# myRelay.net
KiCad netlist of a schematic drawn in EAGLE
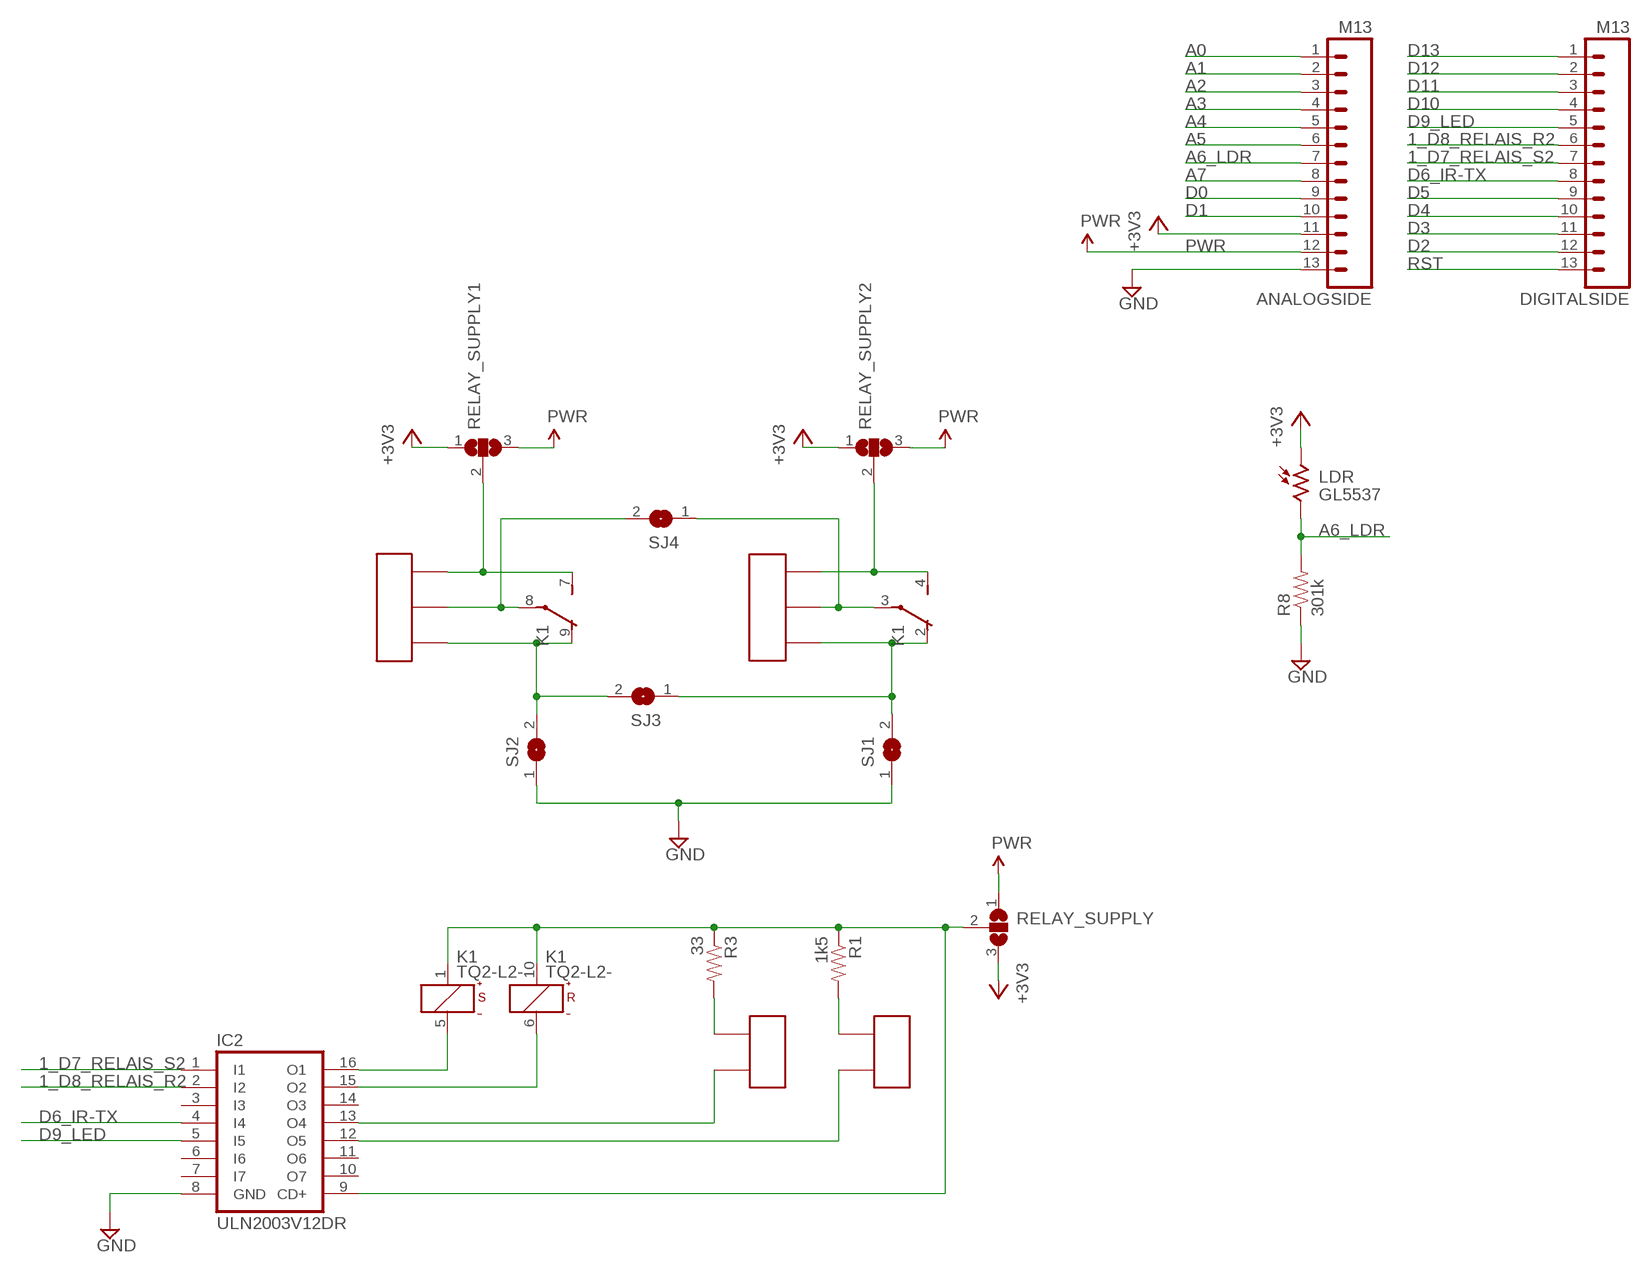
[diagram p0: schematic, sheet 1]

(export (version "E")
  (design (tool "Eeschema 10.0.6"))
  (components
    (comp (ref "ANALOGSIDE")
      (value "M13")
      (footprint "eagle-import:1X13")
      (libsource (lib "eagle-import") (part "M13"))
    )
    (comp (ref "DIGITALSIDE")
      (value "M13")
      (footprint "eagle-import:1X13")
      (libsource (lib "eagle-import") (part "M13"))
    )
    (comp (ref "IC2")
      (value "ULN2003V12DR")
      (footprint "eagle-import:SO16")
      (libsource (lib "eagle-import") (part "ULN2003AD"))
    )
    (comp (ref "K1")
      (value "TQ2-L2-")
      (footprint "eagle-import:TQ2")
      (fields
        (field (name "MF") "AROMAT/ MATSUSHITA")
        (field (name "MPN") "TQ2-L2-9V")
        (field (name "BUERKLIN") "30 G 7570")
        (field (name "MPN_1") "TQ2-L2-3V")
      )
      (libsource (lib "eagle-import") (part "TQ2?-L2-"))
    )
    (comp (ref "LDR")
      (value "GL5537")
      (footprint "eagle-import:M9960")
      (libsource (lib "eagle-import") (part "M9960_11A"))
    )
    (comp (ref "R1")
      (value "1k5")
      (footprint "eagle-import:0603-RES")
      (libsource (lib "eagle-import") (part "RESISTOR0603-RES"))
    )
    (comp (ref "R3")
      (value "33")
      (footprint "eagle-import:0603-RES")
      (libsource (lib "eagle-import") (part "RESISTOR0603-RES"))
    )
    (comp (ref "R8")
      (value "301k")
      (footprint "eagle-import:0603-RES")
      (libsource (lib "eagle-import") (part "RESISTOR0603-RES"))
    )
    (comp (ref "RELAY_SUPPLY")
      (value "SJ2WW")
      (footprint "eagle-import:SJ_2W")
      (libsource (lib "eagle-import") (part "SJ2WW"))
    )
    (comp (ref "RELAY_SUPPLY1")
      (value "SJ2WW")
      (footprint "eagle-import:SJ_2W")
      (libsource (lib "eagle-import") (part "SJ2WW"))
    )
    (comp (ref "RELAY_SUPPLY2")
      (value "SJ2WW")
      (footprint "eagle-import:SJ_2W")
      (libsource (lib "eagle-import") (part "SJ2WW"))
    )
    (comp (ref "SJ1")
      (value "SJW")
      (footprint "eagle-import:SJW")
      (libsource (lib "eagle-import") (part "SJW"))
    )
    (comp (ref "SJ2")
      (value "SJW")
      (footprint "eagle-import:SJW")
      (libsource (lib "eagle-import") (part "SJW"))
    )
    (comp (ref "SJ3")
      (value "SJW")
      (footprint "eagle-import:SJW")
      (libsource (lib "eagle-import") (part "SJW"))
    )
    (comp (ref "SJ4")
      (value "SJW")
      (footprint "eagle-import:SJW")
      (libsource (lib "eagle-import") (part "SJW"))
    )
    (comp (ref "U$1")
      (value "HDR_3PINLUMBERG_KRMC")
      (footprint "eagle-import:1X03_LUMBERG-KRMC_3,5MM")
      (libsource (lib "eagle-import") (part "HDR_3PINLUMBERG_KRMC"))
    )
    (comp (ref "U$2")
      (value "HDR_3PINLUMBERG_KRMC")
      (footprint "eagle-import:1X03_LUMBERG-KRMC_3,5MM")
      (libsource (lib "eagle-import") (part "HDR_3PINLUMBERG_KRMC"))
    )
    (comp (ref "U$3")
      (value "HDR_2PIN")
      (footprint "eagle-import:1X02_NS")
      (libsource (lib "eagle-import") (part "HDR_2PIN"))
    )
    (comp (ref "U$4")
      (value "HDR_2PIN")
      (footprint "eagle-import:1X02_NS")
      (libsource (lib "eagle-import") (part "HDR_2PIN"))
    )
  )
  (nets
    (net (code "1") (name "+3V3") (class "Default")
      (node (ref "ANALOGSIDE") (pin "11") (pinfunction "11_11") (pintype "passive"))
      (node (ref "LDR") (pin "1") (pinfunction "1_1") (pintype "passive"))
      (node (ref "RELAY_SUPPLY") (pin "3") (pinfunction "3_3") (pintype "passive"))
      (node (ref "RELAY_SUPPLY1") (pin "1") (pinfunction "1_1") (pintype "passive"))
      (node (ref "RELAY_SUPPLY2") (pin "1") (pinfunction "1_1") (pintype "passive"))
    )
    (net (code "2") (name "/1_D7_RELAIS_S2") (class "Default")
      (node (ref "DIGITALSIDE") (pin "7") (pinfunction "7_7") (pintype "passive"))
      (node (ref "IC2") (pin "1") (pinfunction "I1_1") (pintype "input"))
    )
    (net (code "3") (name "/1_D8_RELAIS_R2") (class "Default")
      (node (ref "DIGITALSIDE") (pin "6") (pinfunction "6_6") (pintype "passive"))
      (node (ref "IC2") (pin "2") (pinfunction "I2_2") (pintype "input"))
    )
    (net (code "4") (name "/A0") (class "Default")
      (node (ref "ANALOGSIDE") (pin "1") (pinfunction "1_1") (pintype "passive"))
    )
    (net (code "5") (name "/A1") (class "Default")
      (node (ref "ANALOGSIDE") (pin "2") (pinfunction "2_2") (pintype "passive"))
    )
    (net (code "6") (name "/A2") (class "Default")
      (node (ref "ANALOGSIDE") (pin "3") (pinfunction "3_3") (pintype "passive"))
    )
    (net (code "7") (name "/A3") (class "Default")
      (node (ref "ANALOGSIDE") (pin "4") (pinfunction "4_4") (pintype "passive"))
    )
    (net (code "8") (name "/A4") (class "Default")
      (node (ref "ANALOGSIDE") (pin "5") (pinfunction "5_5") (pintype "passive"))
    )
    (net (code "9") (name "/A5") (class "Default")
      (node (ref "ANALOGSIDE") (pin "6") (pinfunction "6_6") (pintype "passive"))
    )
    (net (code "10") (name "/A6_LDR") (class "Default")
      (node (ref "ANALOGSIDE") (pin "7") (pinfunction "7_7") (pintype "passive"))
      (node (ref "LDR") (pin "2") (pinfunction "2_2") (pintype "passive"))
      (node (ref "R8") (pin "2") (pinfunction "2_2") (pintype "passive"))
    )
    (net (code "11") (name "/A7") (class "Default")
      (node (ref "ANALOGSIDE") (pin "8") (pinfunction "8_8") (pintype "passive"))
    )
    (net (code "12") (name "/D0") (class "Default")
      (node (ref "ANALOGSIDE") (pin "9") (pinfunction "9_9") (pintype "passive"))
    )
    (net (code "13") (name "/D1") (class "Default")
      (node (ref "ANALOGSIDE") (pin "10") (pinfunction "10_10") (pintype "passive"))
    )
    (net (code "14") (name "/D2") (class "Default")
      (node (ref "DIGITALSIDE") (pin "12") (pinfunction "12_12") (pintype "passive"))
    )
    (net (code "15") (name "/D3") (class "Default")
      (node (ref "DIGITALSIDE") (pin "11") (pinfunction "11_11") (pintype "passive"))
    )
    (net (code "16") (name "/D4") (class "Default")
      (node (ref "DIGITALSIDE") (pin "10") (pinfunction "10_10") (pintype "passive"))
    )
    (net (code "17") (name "/D5") (class "Default")
      (node (ref "DIGITALSIDE") (pin "9") (pinfunction "9_9") (pintype "passive"))
    )
    (net (code "18") (name "/D6_IR-TX") (class "Default")
      (node (ref "DIGITALSIDE") (pin "8") (pinfunction "8_8") (pintype "passive"))
      (node (ref "IC2") (pin "4") (pinfunction "I4_4") (pintype "input"))
    )
    (net (code "19") (name "/D9_LED") (class "Default")
      (node (ref "DIGITALSIDE") (pin "5") (pinfunction "5_5") (pintype "passive"))
      (node (ref "IC2") (pin "5") (pinfunction "I5_5") (pintype "input"))
    )
    (net (code "20") (name "/D10") (class "Default")
      (node (ref "DIGITALSIDE") (pin "4") (pinfunction "4_4") (pintype "passive"))
    )
    (net (code "21") (name "/D11") (class "Default")
      (node (ref "DIGITALSIDE") (pin "3") (pinfunction "3_3") (pintype "passive"))
    )
    (net (code "22") (name "/D12") (class "Default")
      (node (ref "DIGITALSIDE") (pin "2") (pinfunction "2_2") (pintype "passive"))
    )
    (net (code "23") (name "/D13") (class "Default")
      (node (ref "DIGITALSIDE") (pin "1") (pinfunction "1_1") (pintype "passive"))
    )
    (net (code "24") (name "/RST") (class "Default")
      (node (ref "DIGITALSIDE") (pin "13") (pinfunction "13_13") (pintype "passive"))
    )
    (net (code "25") (name "GND") (class "Default")
      (node (ref "ANALOGSIDE") (pin "13") (pinfunction "13_13") (pintype "passive"))
      (node (ref "IC2") (pin "8") (pinfunction "GND_8") (pintype "power_in"))
      (node (ref "R8") (pin "1") (pinfunction "1_1") (pintype "passive"))
      (node (ref "SJ1") (pin "1") (pinfunction "1_1") (pintype "passive"))
      (node (ref "SJ2") (pin "1") (pinfunction "1_1") (pintype "passive"))
    )
    (net (code "26") (name "Net-(IC2-CD+)") (class "Default")
      (node (ref "IC2") (pin "9") (pinfunction "CD+_9") (pintype "passive"))
      (node (ref "K1") (pin "1") (pinfunction "+_1") (pintype "passive"))
      (node (ref "K1") (pin "10") (pinfunction "+_10") (pintype "passive"))
      (node (ref "R1") (pin "1") (pinfunction "1_1") (pintype "passive"))
      (node (ref "R3") (pin "1") (pinfunction "1_1") (pintype "passive"))
      (node (ref "RELAY_SUPPLY") (pin "2") (pinfunction "2_2") (pintype "passive"))
    )
    (net (code "27") (name "Net-(IC2-O1)") (class "Default")
      (node (ref "IC2") (pin "16") (pinfunction "O1_16") (pintype "open_collector"))
      (node (ref "K1") (pin "5") (pinfunction "-_5") (pintype "passive"))
    )
    (net (code "28") (name "Net-(IC2-O2)") (class "Default")
      (node (ref "IC2") (pin "15") (pinfunction "O2_15") (pintype "open_collector"))
      (node (ref "K1") (pin "6") (pinfunction "-_6") (pintype "passive"))
    )
    (net (code "29") (name "Net-(IC2-O4)") (class "Default")
      (node (ref "IC2") (pin "13") (pinfunction "O4_13") (pintype "open_collector"))
      (node (ref "U$3") (pin "2") (pinfunction "P$2_2") (pintype "bidirectional"))
    )
    (net (code "30") (name "Net-(IC2-O5)") (class "Default")
      (node (ref "IC2") (pin "12") (pinfunction "O5_12") (pintype "open_collector"))
      (node (ref "U$4") (pin "2") (pinfunction "P$2_2") (pintype "bidirectional"))
    )
    (net (code "31") (name "Net-(K1A-O)") (class "Default")
      (node (ref "K1") (pin "2") (pinfunction "O_2") (pintype "passive"))
      (node (ref "SJ1") (pin "2") (pinfunction "2_2") (pintype "passive"))
      (node (ref "SJ3") (pin "1") (pinfunction "1_1") (pintype "passive"))
      (node (ref "U$2") (pin "3") (pinfunction "P$3_3") (pintype "bidirectional"))
    )
    (net (code "32") (name "Net-(K1A-P)") (class "Default")
      (node (ref "K1") (pin "3") (pinfunction "P_3") (pintype "passive"))
      (node (ref "SJ4") (pin "1") (pinfunction "1_1") (pintype "passive"))
      (node (ref "U$2") (pin "2") (pinfunction "P$2_2") (pintype "bidirectional"))
    )
    (net (code "33") (name "Net-(K1A-S)") (class "Default")
      (node (ref "K1") (pin "4") (pinfunction "S_4") (pintype "passive"))
      (node (ref "RELAY_SUPPLY2") (pin "2") (pinfunction "2_2") (pintype "passive"))
      (node (ref "U$2") (pin "1") (pinfunction "P$1_1") (pintype "bidirectional"))
    )
    (net (code "34") (name "Net-(K1B-O)") (class "Default")
      (node (ref "K1") (pin "9") (pinfunction "O_9") (pintype "passive"))
      (node (ref "SJ2") (pin "2") (pinfunction "2_2") (pintype "passive"))
      (node (ref "SJ3") (pin "2") (pinfunction "2_2") (pintype "passive"))
      (node (ref "U$1") (pin "1") (pinfunction "P$1_1") (pintype "bidirectional"))
    )
    (net (code "35") (name "Net-(K1B-P)") (class "Default")
      (node (ref "K1") (pin "8") (pinfunction "P_8") (pintype "passive"))
      (node (ref "SJ4") (pin "2") (pinfunction "2_2") (pintype "passive"))
      (node (ref "U$1") (pin "2") (pinfunction "P$2_2") (pintype "bidirectional"))
    )
    (net (code "36") (name "Net-(K1B-S)") (class "Default")
      (node (ref "K1") (pin "7") (pinfunction "S_7") (pintype "passive"))
      (node (ref "RELAY_SUPPLY1") (pin "2") (pinfunction "2_2") (pintype "passive"))
      (node (ref "U$1") (pin "3") (pinfunction "P$3_3") (pintype "bidirectional"))
    )
    (net (code "37") (name "Net-(U$3-P$1)") (class "Default")
      (node (ref "R3") (pin "2") (pinfunction "2_2") (pintype "passive"))
      (node (ref "U$3") (pin "1") (pinfunction "P$1_1") (pintype "bidirectional"))
    )
    (net (code "38") (name "Net-(U$4-P$1)") (class "Default")
      (node (ref "R1") (pin "2") (pinfunction "2_2") (pintype "passive"))
      (node (ref "U$4") (pin "1") (pinfunction "P$1_1") (pintype "bidirectional"))
    )
    (net (code "39") (name "PWR") (class "Default")
      (node (ref "ANALOGSIDE") (pin "12") (pinfunction "12_12") (pintype "passive"))
      (node (ref "RELAY_SUPPLY") (pin "1") (pinfunction "1_1") (pintype "passive"))
      (node (ref "RELAY_SUPPLY1") (pin "3") (pinfunction "3_3") (pintype "passive"))
      (node (ref "RELAY_SUPPLY2") (pin "3") (pinfunction "3_3") (pintype "passive"))
    )
    (net (code "40") (name "unconnected-(IC2-I3-Pad3)") (class "Default")
      (node (ref "IC2") (pin "3") (pinfunction "I3_3") (pintype "input"))
    )
    (net (code "41") (name "unconnected-(IC2-I6-Pad6)") (class "Default")
      (node (ref "IC2") (pin "6") (pinfunction "I6_6") (pintype "input"))
    )
    (net (code "42") (name "unconnected-(IC2-I7-Pad7)") (class "Default")
      (node (ref "IC2") (pin "7") (pinfunction "I7_7") (pintype "input"))
    )
    (net (code "43") (name "unconnected-(IC2-O3-Pad14)") (class "Default")
      (node (ref "IC2") (pin "14") (pinfunction "O3_14") (pintype "open_collector"))
    )
    (net (code "44") (name "unconnected-(IC2-O6-Pad11)") (class "Default")
      (node (ref "IC2") (pin "11") (pinfunction "O6_11") (pintype "open_collector"))
    )
    (net (code "45") (name "unconnected-(IC2-O7-Pad10)") (class "Default")
      (node (ref "IC2") (pin "10") (pinfunction "O7_10") (pintype "open_collector"))
    )
  )
)
